# snc98_3x4_Switch-futuba.net
KiCad netlist of a schematic drawn in EAGLE
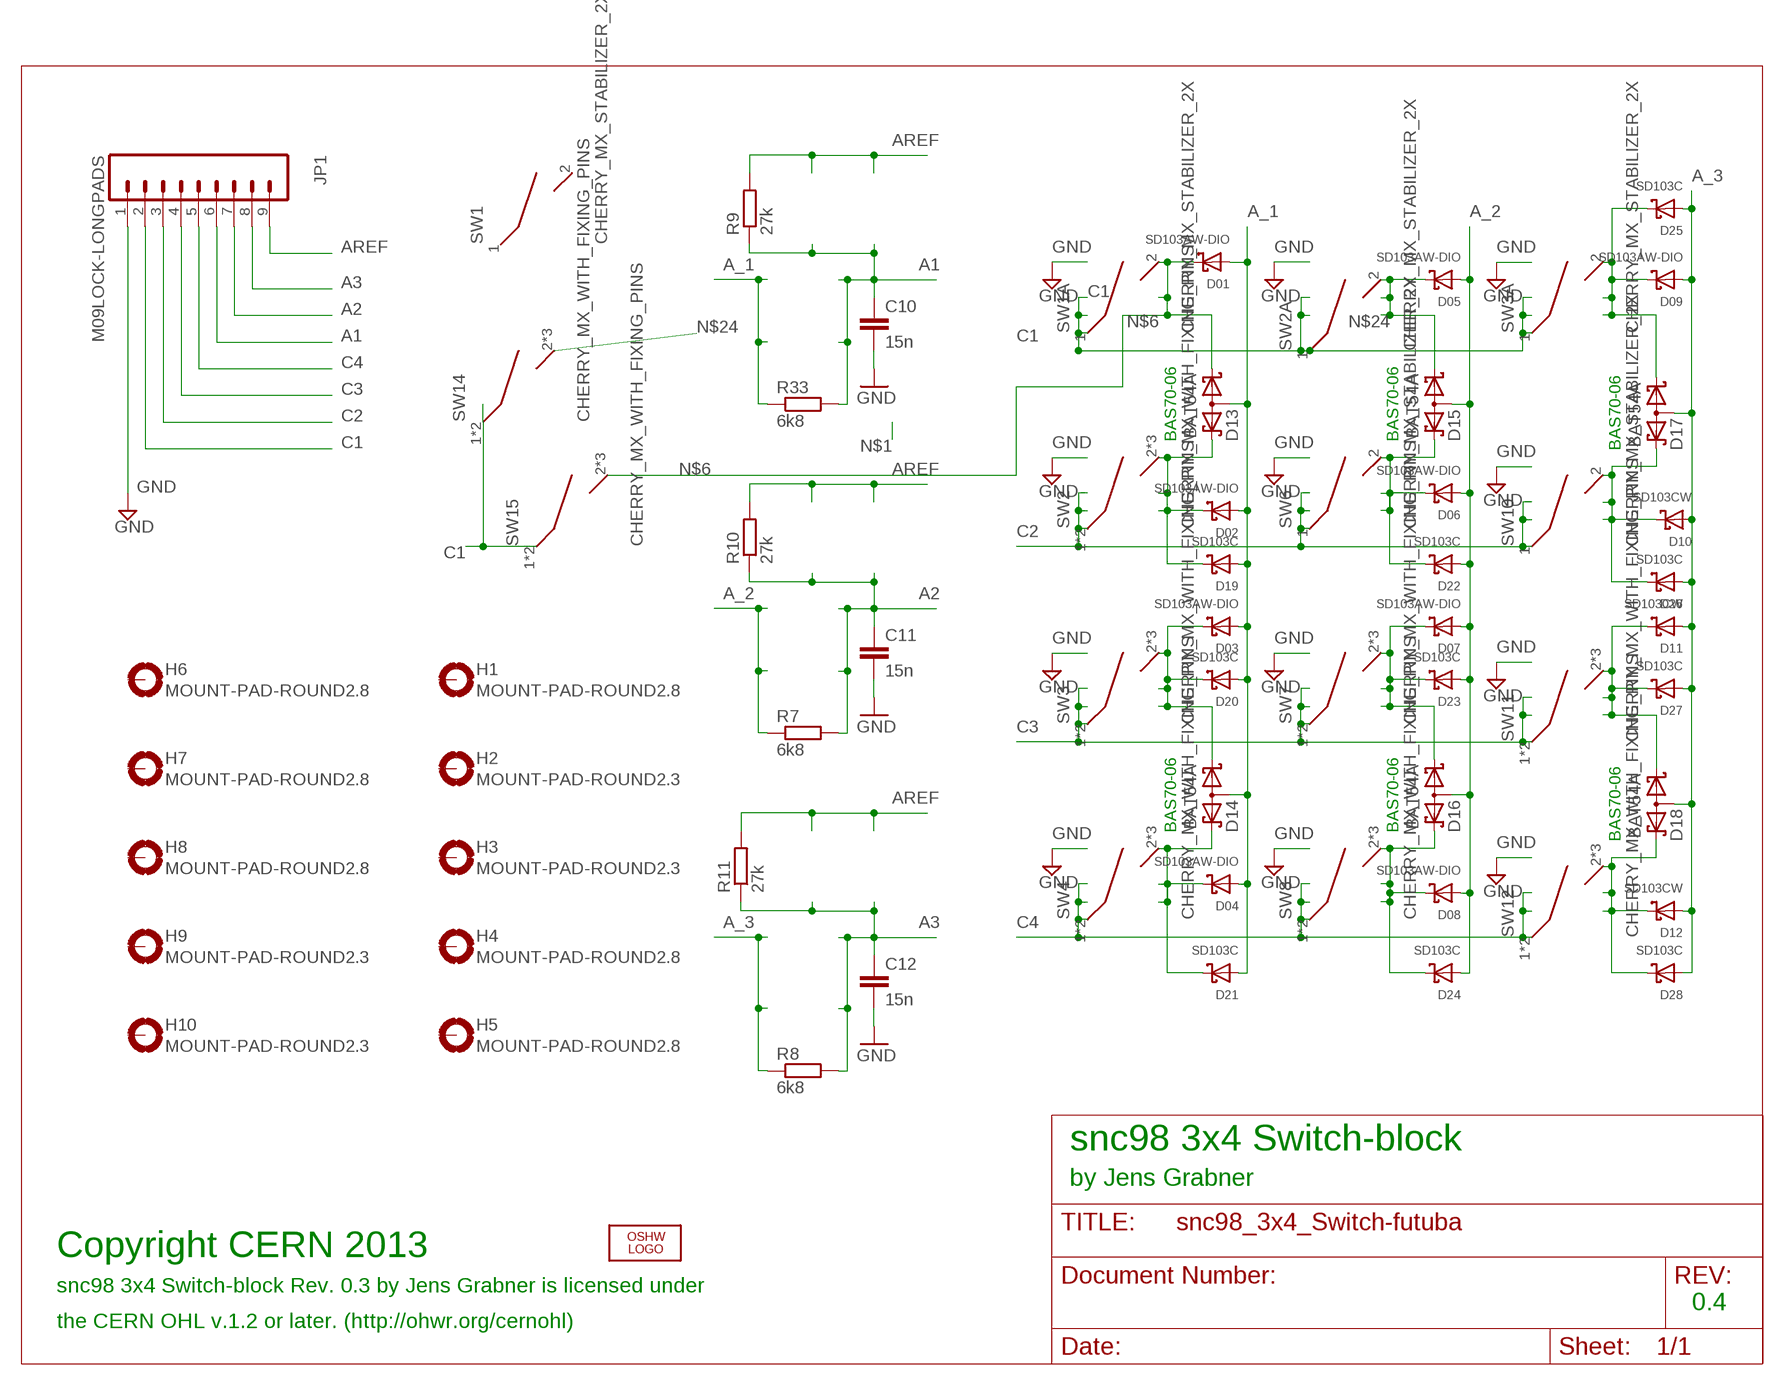
[diagram p0: schematic, sheet 1]

(export (version "E")
  (design (tool "Eeschema 10.0.6"))
  (components
    (comp (ref "C10")
      (value "15n")
      (footprint "eagle-import:C1206K")
      (libsource (lib "eagle-import") (part "C-EUC1206K"))
    )
    (comp (ref "C11")
      (value "15n")
      (footprint "eagle-import:C1206K")
      (libsource (lib "eagle-import") (part "C-EUC1206K"))
    )
    (comp (ref "C12")
      (value "15n")
      (footprint "eagle-import:C1206K")
      (libsource (lib "eagle-import") (part "C-EUC1206K"))
    )
    (comp (ref "D01")
      (value "SD103AW-DIO")
      (footprint "eagle-import:SOD-123F")
      (fields (field (name "MF") "MULTICOMP") (field (name "MPN") "SD103CW-7-F"))
      (libsource (lib "eagle-import") (part "DIODESOD-123F"))
    )
    (comp (ref "D02")
      (value "SD103AW-DIO")
      (footprint "eagle-import:SOD-123F")
      (fields (field (name "MF") "MULTICOMP") (field (name "MPN") "SD103CW-7-F"))
      (libsource (lib "eagle-import") (part "DIODESOD-123F"))
    )
    (comp (ref "D03")
      (value "SD103AW-DIO")
      (footprint "eagle-import:SOD-123F")
      (fields (field (name "MF") "MULTICOMP") (field (name "MPN") "SD103CW-7-F"))
      (libsource (lib "eagle-import") (part "DIODESOD-123F"))
    )
    (comp (ref "D04")
      (value "SD103AW-DIO")
      (footprint "eagle-import:SOD-123F")
      (fields (field (name "MF") "MULTICOMP") (field (name "MPN") "SD103CW-7-F"))
      (libsource (lib "eagle-import") (part "DIODESOD-123F"))
    )
    (comp (ref "D05")
      (value "SD103AW-DIO")
      (footprint "eagle-import:SOD-123F")
      (fields (field (name "MF") "MULTICOMP") (field (name "MPN") "SD103CW-7-F"))
      (libsource (lib "eagle-import") (part "DIODESOD-123F"))
    )
    (comp (ref "D06")
      (value "SD103AW-DIO")
      (footprint "eagle-import:SOD-123F")
      (fields (field (name "MF") "MULTICOMP") (field (name "MPN") "SD103CW-7-F"))
      (libsource (lib "eagle-import") (part "DIODESOD-123F"))
    )
    (comp (ref "D07")
      (value "SD103AW-DIO")
      (footprint "eagle-import:SOD-123F")
      (fields (field (name "MF") "MULTICOMP") (field (name "MPN") "SD103CW-7-F"))
      (libsource (lib "eagle-import") (part "DIODESOD-123F"))
    )
    (comp (ref "D08")
      (value "SD103AW-DIO")
      (footprint "eagle-import:SOD-123F")
      (fields (field (name "MF") "MULTICOMP") (field (name "MPN") "SD103CW-7-F"))
      (libsource (lib "eagle-import") (part "DIODESOD-123F"))
    )
    (comp (ref "D09")
      (value "SD103AW-DIO")
      (footprint "eagle-import:SOD-123F")
      (fields (field (name "MF") "MULTICOMP") (field (name "MPN") "SD103CW-7-F"))
      (libsource (lib "eagle-import") (part "DIODESOD-123F"))
    )
    (comp (ref "D10")
      (value "SD103CW")
      (footprint "eagle-import:SOD-123F")
      (fields (field (name "MF") "MULTICOMP") (field (name "MPN") "SD103CW-7-F"))
      (libsource (lib "eagle-import") (part "DIODESOD-123F"))
    )
    (comp (ref "D11")
      (value "SD103CW")
      (footprint "eagle-import:SOD-123F")
      (fields (field (name "MF") "MULTICOMP") (field (name "MPN") "SD103CW-7-F"))
      (libsource (lib "eagle-import") (part "DIODESOD-123F"))
    )
    (comp (ref "D12")
      (value "SD103CW")
      (footprint "eagle-import:SOD-123F")
      (fields (field (name "MF") "MULTICOMP") (field (name "MPN") "SD103CW-7-F"))
      (libsource (lib "eagle-import") (part "DIODESOD-123F"))
    )
    (comp (ref "D13")
      (value "BAT54A")
      (footprint "eagle-import:SOT23")
      (libsource (lib "eagle-import") (part "BAT54A"))
    )
    (comp (ref "D14")
      (value "BAT54A")
      (footprint "eagle-import:SOT23")
      (libsource (lib "eagle-import") (part "BAT54A"))
    )
    (comp (ref "D15")
      (value "BAT54A")
      (footprint "eagle-import:SOT23")
      (libsource (lib "eagle-import") (part "BAT54A"))
    )
    (comp (ref "D16")
      (value "BAT54A")
      (footprint "eagle-import:SOT23")
      (libsource (lib "eagle-import") (part "BAT54A"))
    )
    (comp (ref "D17")
      (value "BAT54A")
      (footprint "eagle-import:SOT23")
      (libsource (lib "eagle-import") (part "BAT54A"))
    )
    (comp (ref "D18")
      (value "BAT54A")
      (footprint "eagle-import:SOT23")
      (libsource (lib "eagle-import") (part "BAT54A"))
    )
    (comp (ref "D19")
      (value "SD103C")
      (footprint "eagle-import:280MIL-TH")
      (fields (field (name "MF") "MULTICOMP") (field (name "MPN") "SD103CW-7-F"))
      (libsource (lib "eagle-import") (part "DIODE280MIL-TH"))
    )
    (comp (ref "D20")
      (value "SD103C")
      (footprint "eagle-import:280MIL-TH")
      (fields (field (name "MF") "MULTICOMP") (field (name "MPN") "SD103CW-7-F"))
      (libsource (lib "eagle-import") (part "DIODE280MIL-TH"))
    )
    (comp (ref "D21")
      (value "SD103C")
      (footprint "eagle-import:280MIL-TH")
      (fields (field (name "MF") "MULTICOMP") (field (name "MPN") "SD103CW-7-F"))
      (libsource (lib "eagle-import") (part "DIODE280MIL-TH"))
    )
    (comp (ref "D22")
      (value "SD103C")
      (footprint "eagle-import:280MIL-TH")
      (fields (field (name "MF") "MULTICOMP") (field (name "MPN") "SD103CW-7-F"))
      (libsource (lib "eagle-import") (part "DIODE280MIL-TH"))
    )
    (comp (ref "D23")
      (value "SD103C")
      (footprint "eagle-import:280MIL-TH")
      (fields (field (name "MF") "MULTICOMP") (field (name "MPN") "SD103CW-7-F"))
      (libsource (lib "eagle-import") (part "DIODE280MIL-TH"))
    )
    (comp (ref "D24")
      (value "SD103C")
      (footprint "eagle-import:280MIL-TH")
      (fields (field (name "MF") "MULTICOMP") (field (name "MPN") "SD103CW-7-F"))
      (libsource (lib "eagle-import") (part "DIODE280MIL-TH"))
    )
    (comp (ref "D25")
      (value "SD103C")
      (footprint "eagle-import:280MIL-TH")
      (fields (field (name "MF") "MULTICOMP") (field (name "MPN") "SD103CW-7-F"))
      (libsource (lib "eagle-import") (part "DIODE280MIL-TH"))
    )
    (comp (ref "D26")
      (value "SD103C")
      (footprint "eagle-import:280MIL-TH")
      (fields (field (name "MF") "MULTICOMP") (field (name "MPN") "SD103CW-7-F"))
      (libsource (lib "eagle-import") (part "DIODE280MIL-TH"))
    )
    (comp (ref "D27")
      (value "SD103C")
      (footprint "eagle-import:280MIL-TH")
      (fields (field (name "MF") "MULTICOMP") (field (name "MPN") "SD103CW-7-F"))
      (libsource (lib "eagle-import") (part "DIODE280MIL-TH"))
    )
    (comp (ref "D28")
      (value "SD103C")
      (footprint "eagle-import:280MIL-TH")
      (fields (field (name "MF") "MULTICOMP") (field (name "MPN") "SD103CW-7-F"))
      (libsource (lib "eagle-import") (part "DIODE280MIL-TH"))
    )
    (comp (ref "H1")
      (value "MOUNT-PAD-ROUND2.8")
      (footprint "eagle-import:2,8-PAD")
      (libsource (lib "eagle-import") (part "MOUNT-PAD-ROUND2.8"))
    )
    (comp (ref "H2")
      (value "MOUNT-PAD-ROUND2.3")
      (footprint "eagle-import:2,3-PAD")
      (libsource (lib "eagle-import") (part "MOUNT-PAD-ROUND2.3"))
    )
    (comp (ref "H3")
      (value "MOUNT-PAD-ROUND2.3")
      (footprint "eagle-import:2,3-PAD")
      (libsource (lib "eagle-import") (part "MOUNT-PAD-ROUND2.3"))
    )
    (comp (ref "H4")
      (value "MOUNT-PAD-ROUND2.8")
      (footprint "eagle-import:2,8-PAD")
      (libsource (lib "eagle-import") (part "MOUNT-PAD-ROUND2.8"))
    )
    (comp (ref "H5")
      (value "MOUNT-PAD-ROUND2.8")
      (footprint "eagle-import:2,8-PAD")
      (libsource (lib "eagle-import") (part "MOUNT-PAD-ROUND2.8"))
    )
    (comp (ref "H6")
      (value "MOUNT-PAD-ROUND2.8")
      (footprint "eagle-import:2,8-PAD")
      (libsource (lib "eagle-import") (part "MOUNT-PAD-ROUND2.8"))
    )
    (comp (ref "H7")
      (value "MOUNT-PAD-ROUND2.8")
      (footprint "eagle-import:2,8-PAD")
      (libsource (lib "eagle-import") (part "MOUNT-PAD-ROUND2.8"))
    )
    (comp (ref "H8")
      (value "MOUNT-PAD-ROUND2.8")
      (footprint "eagle-import:2,8-PAD")
      (libsource (lib "eagle-import") (part "MOUNT-PAD-ROUND2.8"))
    )
    (comp (ref "H9")
      (value "MOUNT-PAD-ROUND2.3")
      (footprint "eagle-import:2,3-PAD")
      (libsource (lib "eagle-import") (part "MOUNT-PAD-ROUND2.3"))
    )
    (comp (ref "H10")
      (value "MOUNT-PAD-ROUND2.3")
      (footprint "eagle-import:2,3-PAD")
      (libsource (lib "eagle-import") (part "MOUNT-PAD-ROUND2.3"))
    )
    (comp (ref "JP1")
      (value "M09LOCK-LONGPADS")
      (footprint "eagle-import:1X09_LOCK_LONGPADS")
      (libsource (lib "eagle-import") (part "M09LOCK-LONGPADS"))
    )
    (comp (ref "LOGO1")
      (value "OSHW_LOGO_8MILX0150-NT")
      (footprint "eagle-import:OSHW_8X150_NOTEXT")
      (libsource (lib "eagle-import") (part "OSHW_LOGO_8MILX0150-NT"))
    )
    (comp (ref "R7")
      (value "6k8")
      (footprint "eagle-import:M0805")
      (libsource (lib "eagle-import") (part "R-EU_M0805"))
    )
    (comp (ref "R8")
      (value "6k8")
      (footprint "eagle-import:M0805")
      (libsource (lib "eagle-import") (part "R-EU_M0805"))
    )
    (comp (ref "R9")
      (value "27k")
      (footprint "eagle-import:M0805")
      (libsource (lib "eagle-import") (part "R-EU_M0805"))
    )
    (comp (ref "R10")
      (value "27k")
      (footprint "eagle-import:M0805")
      (libsource (lib "eagle-import") (part "R-EU_M0805"))
    )
    (comp (ref "R11")
      (value "27k")
      (footprint "eagle-import:M0805")
      (libsource (lib "eagle-import") (part "R-EU_M0805"))
    )
    (comp (ref "R33")
      (value "6k8")
      (footprint "eagle-import:M0805")
      (libsource (lib "eagle-import") (part "R-EU_M0805"))
    )
    (comp (ref "SW1")
      (value "CHERRY_MX_STABILIZER_2X")
      (footprint "eagle-import:MX1A-XXNN_WITH_STABILIZER_2X")
      (libsource (lib "eagle-import") (part "CHERRY_MX_STABILIZER_2X"))
    )
    (comp (ref "SW1A")
      (value "CHERRY_MX_STABILIZER_2X")
      (footprint "eagle-import:MX1A-XXNN_WITH_STABILIZER_2X")
      (libsource (lib "eagle-import") (part "CHERRY_MX_STABILIZER_2X"))
    )
    (comp (ref "SW2")
      (value "CHERRY_MX_WITH_FIXING_PINS")
      (footprint "eagle-import:MX1A-XXNW")
      (libsource (lib "eagle-import") (part "CHERRY_MX_WITH_FIXING_PINS"))
    )
    (comp (ref "SW2A")
      (value "CHERRY_MX_STABILIZER_2X")
      (footprint "eagle-import:MX1A-XXNN_WITH_STABILIZER_2X")
      (libsource (lib "eagle-import") (part "CHERRY_MX_STABILIZER_2X"))
    )
    (comp (ref "SW3")
      (value "CHERRY_MX_WITH_FIXING_PINS")
      (footprint "eagle-import:MX1A-XXNW")
      (libsource (lib "eagle-import") (part "CHERRY_MX_WITH_FIXING_PINS"))
    )
    (comp (ref "SW3A")
      (value "CHERRY_MX_STABILIZER_2X")
      (footprint "eagle-import:MX1A-XXNN_WITH_STABILIZER_2X")
      (libsource (lib "eagle-import") (part "CHERRY_MX_STABILIZER_2X"))
    )
    (comp (ref "SW4")
      (value "CHERRY_MX_WITH_FIXING_PINS")
      (footprint "eagle-import:MX1A-XXNW")
      (libsource (lib "eagle-import") (part "CHERRY_MX_WITH_FIXING_PINS"))
    )
    (comp (ref "SW6")
      (value "CHERRY_MX_STABILIZER_2X")
      (footprint "eagle-import:MX1A-XXNN_WITH_STABILIZER_2X")
      (libsource (lib "eagle-import") (part "CHERRY_MX_STABILIZER_2X"))
    )
    (comp (ref "SW7")
      (value "CHERRY_MX_WITH_FIXING_PINS")
      (footprint "eagle-import:MX1A-XXNW")
      (libsource (lib "eagle-import") (part "CHERRY_MX_WITH_FIXING_PINS"))
    )
    (comp (ref "SW8")
      (value "CHERRY_MX_WITH_FIXING_PINS")
      (footprint "eagle-import:MX1A-XXNW")
      (libsource (lib "eagle-import") (part "CHERRY_MX_WITH_FIXING_PINS"))
    )
    (comp (ref "SW10")
      (value "CHERRY_MX_STABILIZER_2X")
      (footprint "eagle-import:MX1A-XXNN_WITH_STABILIZER_2X")
      (libsource (lib "eagle-import") (part "CHERRY_MX_STABILIZER_2X"))
    )
    (comp (ref "SW11")
      (value "CHERRY_MX_WITH_FIXING_PINS")
      (footprint "eagle-import:MX1A-XXNW")
      (libsource (lib "eagle-import") (part "CHERRY_MX_WITH_FIXING_PINS"))
    )
    (comp (ref "SW12")
      (value "CHERRY_MX_WITH_FIXING_PINS")
      (footprint "eagle-import:MX1A-XXNW")
      (libsource (lib "eagle-import") (part "CHERRY_MX_WITH_FIXING_PINS"))
    )
    (comp (ref "SW14")
      (value "CHERRY_MX_WITH_FIXING_PINS")
      (footprint "eagle-import:MX1A-XXNW")
      (libsource (lib "eagle-import") (part "CHERRY_MX_WITH_FIXING_PINS"))
    )
    (comp (ref "SW15")
      (value "CHERRY_MX_WITH_FIXING_PINS")
      (footprint "eagle-import:MX1A-XXNW")
      (libsource (lib "eagle-import") (part "CHERRY_MX_WITH_FIXING_PINS"))
    )
  )
  (nets
    (net (code "1") (name "/A1") (class "Default")
      (node (ref "C10") (pin "1") (pinfunction "1_1") (pintype "passive"))
      (node (ref "JP1") (pin "6") (pinfunction "6_6") (pintype "passive"))
      (node (ref "R33") (pin "2") (pinfunction "2_2") (pintype "passive"))
      (node (ref "R9") (pin "1") (pinfunction "1_1") (pintype "passive"))
    )
    (net (code "2") (name "/A2") (class "Default")
      (node (ref "C11") (pin "1") (pinfunction "1_1") (pintype "passive"))
      (node (ref "JP1") (pin "7") (pinfunction "7_7") (pintype "passive"))
      (node (ref "R10") (pin "1") (pinfunction "1_1") (pintype "passive"))
      (node (ref "R7") (pin "2") (pinfunction "2_2") (pintype "passive"))
    )
    (net (code "3") (name "/A3") (class "Default")
      (node (ref "C12") (pin "1") (pinfunction "1_1") (pintype "passive"))
      (node (ref "JP1") (pin "8") (pinfunction "8_8") (pintype "passive"))
      (node (ref "R11") (pin "1") (pinfunction "1_1") (pintype "passive"))
      (node (ref "R8") (pin "2") (pinfunction "2_2") (pintype "passive"))
    )
    (net (code "4") (name "/AREF") (class "Default")
      (node (ref "JP1") (pin "9") (pinfunction "9_9") (pintype "passive"))
      (node (ref "R10") (pin "2") (pinfunction "2_2") (pintype "passive"))
      (node (ref "R11") (pin "2") (pinfunction "2_2") (pintype "passive"))
      (node (ref "R9") (pin "2") (pinfunction "2_2") (pintype "passive"))
    )
    (net (code "5") (name "/A_1") (class "Default")
      (node (ref "D01") (pin "A") (pinfunction "A_A") (pintype "passive"))
      (node (ref "D02") (pin "A") (pinfunction "A_A") (pintype "passive"))
      (node (ref "D03") (pin "A") (pinfunction "A_A") (pintype "passive"))
      (node (ref "D04") (pin "A") (pinfunction "A_A") (pintype "passive"))
      (node (ref "D13") (pin "3") (pinfunction "AA_3") (pintype "passive"))
      (node (ref "D14") (pin "3") (pinfunction "AA_3") (pintype "passive"))
      (node (ref "D19") (pin "P$1") (pinfunction "A_P$1") (pintype "passive"))
      (node (ref "D20") (pin "P$1") (pinfunction "A_P$1") (pintype "passive"))
      (node (ref "D21") (pin "P$1") (pinfunction "A_P$1") (pintype "passive"))
      (node (ref "R33") (pin "1") (pinfunction "1_1") (pintype "passive"))
    )
    (net (code "6") (name "/A_2") (class "Default")
      (node (ref "D05") (pin "A") (pinfunction "A_A") (pintype "passive"))
      (node (ref "D06") (pin "A") (pinfunction "A_A") (pintype "passive"))
      (node (ref "D07") (pin "A") (pinfunction "A_A") (pintype "passive"))
      (node (ref "D08") (pin "A") (pinfunction "A_A") (pintype "passive"))
      (node (ref "D15") (pin "3") (pinfunction "AA_3") (pintype "passive"))
      (node (ref "D16") (pin "3") (pinfunction "AA_3") (pintype "passive"))
      (node (ref "D22") (pin "P$1") (pinfunction "A_P$1") (pintype "passive"))
      (node (ref "D23") (pin "P$1") (pinfunction "A_P$1") (pintype "passive"))
      (node (ref "D24") (pin "P$1") (pinfunction "A_P$1") (pintype "passive"))
      (node (ref "R7") (pin "1") (pinfunction "1_1") (pintype "passive"))
    )
    (net (code "7") (name "/A_3") (class "Default")
      (node (ref "D09") (pin "A") (pinfunction "A_A") (pintype "passive"))
      (node (ref "D10") (pin "A") (pinfunction "A_A") (pintype "passive"))
      (node (ref "D11") (pin "A") (pinfunction "A_A") (pintype "passive"))
      (node (ref "D12") (pin "A") (pinfunction "A_A") (pintype "passive"))
      (node (ref "D17") (pin "3") (pinfunction "AA_3") (pintype "passive"))
      (node (ref "D18") (pin "3") (pinfunction "AA_3") (pintype "passive"))
      (node (ref "D25") (pin "P$1") (pinfunction "A_P$1") (pintype "passive"))
      (node (ref "D26") (pin "P$1") (pinfunction "A_P$1") (pintype "passive"))
      (node (ref "D27") (pin "P$1") (pinfunction "A_P$1") (pintype "passive"))
      (node (ref "D28") (pin "P$1") (pinfunction "A_P$1") (pintype "passive"))
      (node (ref "R8") (pin "1") (pinfunction "1_1") (pintype "passive"))
    )
    (net (code "8") (name "/C1") (class "Default")
      (node (ref "JP1") (pin "2") (pinfunction "2_2") (pintype "passive"))
      (node (ref "SW14") (pin "1") (pinfunction "1_1") (pintype "passive"))
      (node (ref "SW14") (pin "3") (pinfunction "1_3") (pintype "passive"))
      (node (ref "SW15") (pin "1") (pinfunction "1_1") (pintype "passive"))
      (node (ref "SW15") (pin "3") (pinfunction "1_3") (pintype "passive"))
      (node (ref "SW1A") (pin "1") (pinfunction "1_1") (pintype "passive"))
      (node (ref "SW2A") (pin "1") (pinfunction "1_1") (pintype "passive"))
      (node (ref "SW3A") (pin "1") (pinfunction "1_1") (pintype "passive"))
    )
    (net (code "9") (name "/C2") (class "Default")
      (node (ref "JP1") (pin "3") (pinfunction "3_3") (pintype "passive"))
      (node (ref "SW10") (pin "1") (pinfunction "1_1") (pintype "passive"))
      (node (ref "SW2") (pin "1") (pinfunction "1_1") (pintype "passive"))
      (node (ref "SW2") (pin "3") (pinfunction "1_3") (pintype "passive"))
      (node (ref "SW6") (pin "1") (pinfunction "1_1") (pintype "passive"))
    )
    (net (code "10") (name "/C3") (class "Default")
      (node (ref "JP1") (pin "4") (pinfunction "4_4") (pintype "passive"))
      (node (ref "SW11") (pin "1") (pinfunction "1_1") (pintype "passive"))
      (node (ref "SW11") (pin "3") (pinfunction "1_3") (pintype "passive"))
      (node (ref "SW3") (pin "1") (pinfunction "1_1") (pintype "passive"))
      (node (ref "SW3") (pin "3") (pinfunction "1_3") (pintype "passive"))
      (node (ref "SW7") (pin "1") (pinfunction "1_1") (pintype "passive"))
      (node (ref "SW7") (pin "3") (pinfunction "1_3") (pintype "passive"))
    )
    (net (code "11") (name "/C4") (class "Default")
      (node (ref "JP1") (pin "5") (pinfunction "5_5") (pintype "passive"))
      (node (ref "SW12") (pin "1") (pinfunction "1_1") (pintype "passive"))
      (node (ref "SW12") (pin "3") (pinfunction "1_3") (pintype "passive"))
      (node (ref "SW4") (pin "1") (pinfunction "1_1") (pintype "passive"))
      (node (ref "SW4") (pin "3") (pinfunction "1_3") (pintype "passive"))
      (node (ref "SW8") (pin "1") (pinfunction "1_1") (pintype "passive"))
      (node (ref "SW8") (pin "3") (pinfunction "1_3") (pintype "passive"))
    )
    (net (code "13") (name "/N$6") (class "Default")
      (node (ref "D01") (pin "C") (pinfunction "C_C") (pintype "passive"))
      (node (ref "D13") (pin "1") (pinfunction "K1_1") (pintype "passive"))
      (node (ref "SW15") (pin "2") (pinfunction "2_2") (pintype "passive"))
      (node (ref "SW15") (pin "4") (pinfunction "2_4") (pintype "passive"))
      (node (ref "SW15") (pin "5") (pinfunction "2_5") (pintype "passive"))
      (node (ref "SW1A") (pin "2") (pinfunction "2_2") (pintype "passive"))
    )
    (net (code "14") (name "/N$24") (class "Default")
      (node (ref "D05") (pin "C") (pinfunction "C_C") (pintype "passive"))
      (node (ref "D15") (pin "1") (pinfunction "K1_1") (pintype "passive"))
      (node (ref "SW14") (pin "2") (pinfunction "2_2") (pintype "passive"))
      (node (ref "SW14") (pin "4") (pinfunction "2_4") (pintype "passive"))
      (node (ref "SW14") (pin "5") (pinfunction "2_5") (pintype "passive"))
      (node (ref "SW2A") (pin "2") (pinfunction "2_2") (pintype "passive"))
    )
    (net (code "15") (name "GND") (class "Default")
      (node (ref "C10") (pin "2") (pinfunction "2_2") (pintype "passive"))
      (node (ref "C11") (pin "2") (pinfunction "2_2") (pintype "passive"))
      (node (ref "C12") (pin "2") (pinfunction "2_2") (pintype "passive"))
      (node (ref "JP1") (pin "1") (pinfunction "1_1") (pintype "passive"))
    )
    (net (code "16") (name "Net-(D13-K2)") (class "Default")
      (node (ref "D02") (pin "C") (pinfunction "C_C") (pintype "passive"))
      (node (ref "D13") (pin "2") (pinfunction "K2_2") (pintype "passive"))
      (node (ref "D19") (pin "P$2") (pinfunction "C_P$2") (pintype "passive"))
      (node (ref "SW2") (pin "2") (pinfunction "2_2") (pintype "passive"))
      (node (ref "SW2") (pin "4") (pinfunction "2_4") (pintype "passive"))
      (node (ref "SW2") (pin "5") (pinfunction "2_5") (pintype "passive"))
    )
    (net (code "17") (name "Net-(D14-K1)") (class "Default")
      (node (ref "D03") (pin "C") (pinfunction "C_C") (pintype "passive"))
      (node (ref "D14") (pin "1") (pinfunction "K1_1") (pintype "passive"))
      (node (ref "D20") (pin "P$2") (pinfunction "C_P$2") (pintype "passive"))
      (node (ref "SW3") (pin "2") (pinfunction "2_2") (pintype "passive"))
      (node (ref "SW3") (pin "4") (pinfunction "2_4") (pintype "passive"))
      (node (ref "SW3") (pin "5") (pinfunction "2_5") (pintype "passive"))
    )
    (net (code "18") (name "Net-(D14-K2)") (class "Default")
      (node (ref "D04") (pin "C") (pinfunction "C_C") (pintype "passive"))
      (node (ref "D14") (pin "2") (pinfunction "K2_2") (pintype "passive"))
      (node (ref "D21") (pin "P$2") (pinfunction "C_P$2") (pintype "passive"))
      (node (ref "SW4") (pin "2") (pinfunction "2_2") (pintype "passive"))
      (node (ref "SW4") (pin "4") (pinfunction "2_4") (pintype "passive"))
      (node (ref "SW4") (pin "5") (pinfunction "2_5") (pintype "passive"))
    )
    (net (code "19") (name "Net-(D15-K2)") (class "Default")
      (node (ref "D06") (pin "C") (pinfunction "C_C") (pintype "passive"))
      (node (ref "D15") (pin "2") (pinfunction "K2_2") (pintype "passive"))
      (node (ref "D22") (pin "P$2") (pinfunction "C_P$2") (pintype "passive"))
      (node (ref "SW6") (pin "2") (pinfunction "2_2") (pintype "passive"))
    )
    (net (code "20") (name "Net-(D16-K1)") (class "Default")
      (node (ref "D07") (pin "C") (pinfunction "C_C") (pintype "passive"))
      (node (ref "D16") (pin "1") (pinfunction "K1_1") (pintype "passive"))
      (node (ref "D23") (pin "P$2") (pinfunction "C_P$2") (pintype "passive"))
      (node (ref "SW7") (pin "2") (pinfunction "2_2") (pintype "passive"))
      (node (ref "SW7") (pin "4") (pinfunction "2_4") (pintype "passive"))
      (node (ref "SW7") (pin "5") (pinfunction "2_5") (pintype "passive"))
    )
    (net (code "21") (name "Net-(D16-K2)") (class "Default")
      (node (ref "D08") (pin "C") (pinfunction "C_C") (pintype "passive"))
      (node (ref "D16") (pin "2") (pinfunction "K2_2") (pintype "passive"))
      (node (ref "D24") (pin "P$2") (pinfunction "C_P$2") (pintype "passive"))
      (node (ref "SW8") (pin "2") (pinfunction "2_2") (pintype "passive"))
      (node (ref "SW8") (pin "4") (pinfunction "2_4") (pintype "passive"))
      (node (ref "SW8") (pin "5") (pinfunction "2_5") (pintype "passive"))
    )
    (net (code "22") (name "Net-(D17-K1)") (class "Default")
      (node (ref "D09") (pin "C") (pinfunction "C_C") (pintype "passive"))
      (node (ref "D17") (pin "1") (pinfunction "K1_1") (pintype "passive"))
      (node (ref "D25") (pin "P$2") (pinfunction "C_P$2") (pintype "passive"))
      (node (ref "SW3A") (pin "2") (pinfunction "2_2") (pintype "passive"))
    )
    (net (code "23") (name "Net-(D17-K2)") (class "Default")
      (node (ref "D10") (pin "C") (pinfunction "C_C") (pintype "passive"))
      (node (ref "D17") (pin "2") (pinfunction "K2_2") (pintype "passive"))
      (node (ref "D26") (pin "P$2") (pinfunction "C_P$2") (pintype "passive"))
      (node (ref "SW10") (pin "2") (pinfunction "2_2") (pintype "passive"))
    )
    (net (code "24") (name "Net-(D18-K1)") (class "Default")
      (node (ref "D11") (pin "C") (pinfunction "C_C") (pintype "passive"))
      (node (ref "D18") (pin "1") (pinfunction "K1_1") (pintype "passive"))
      (node (ref "D27") (pin "P$2") (pinfunction "C_P$2") (pintype "passive"))
      (node (ref "SW11") (pin "2") (pinfunction "2_2") (pintype "passive"))
      (node (ref "SW11") (pin "4") (pinfunction "2_4") (pintype "passive"))
      (node (ref "SW11") (pin "5") (pinfunction "2_5") (pintype "passive"))
    )
    (net (code "25") (name "Net-(D18-K2)") (class "Default")
      (node (ref "D12") (pin "C") (pinfunction "C_C") (pintype "passive"))
      (node (ref "D18") (pin "2") (pinfunction "K2_2") (pintype "passive"))
      (node (ref "D28") (pin "P$2") (pinfunction "C_P$2") (pintype "passive"))
      (node (ref "SW12") (pin "2") (pinfunction "2_2") (pintype "passive"))
      (node (ref "SW12") (pin "4") (pinfunction "2_4") (pintype "passive"))
      (node (ref "SW12") (pin "5") (pinfunction "2_5") (pintype "passive"))
    )
    (net (code "26") (name "unconnected-(H1-MOUNT-PadB2,8)") (class "Default")
      (node (ref "H1") (pin "B2,8") (pinfunction "MOUNT_B2,8") (pintype "passive"))
    )
    (net (code "27") (name "unconnected-(H2-MOUNT-PadB2,8)") (class "Default")
      (node (ref "H2") (pin "B2,8") (pinfunction "MOUNT_B2,8") (pintype "passive"))
    )
    (net (code "28") (name "unconnected-(H3-MOUNT-PadB2,8)") (class "Default")
      (node (ref "H3") (pin "B2,8") (pinfunction "MOUNT_B2,8") (pintype "passive"))
    )
    (net (code "29") (name "unconnected-(H4-MOUNT-PadB2,8)") (class "Default")
      (node (ref "H4") (pin "B2,8") (pinfunction "MOUNT_B2,8") (pintype "passive"))
    )
    (net (code "30") (name "unconnected-(H5-MOUNT-PadB2,8)") (class "Default")
      (node (ref "H5") (pin "B2,8") (pinfunction "MOUNT_B2,8") (pintype "passive"))
    )
    (net (code "31") (name "unconnected-(H6-MOUNT-PadB2,8)") (class "Default")
      (node (ref "H6") (pin "B2,8") (pinfunction "MOUNT_B2,8") (pintype "passive"))
    )
    (net (code "32") (name "unconnected-(H7-MOUNT-PadB2,8)") (class "Default")
      (node (ref "H7") (pin "B2,8") (pinfunction "MOUNT_B2,8") (pintype "passive"))
    )
    (net (code "33") (name "unconnected-(H8-MOUNT-PadB2,8)") (class "Default")
      (node (ref "H8") (pin "B2,8") (pinfunction "MOUNT_B2,8") (pintype "passive"))
    )
    (net (code "34") (name "unconnected-(H9-MOUNT-PadB2,8)") (class "Default")
      (node (ref "H9") (pin "B2,8") (pinfunction "MOUNT_B2,8") (pintype "passive"))
    )
    (net (code "35") (name "unconnected-(H10-MOUNT-PadB2,8)") (class "Default")
      (node (ref "H10") (pin "B2,8") (pinfunction "MOUNT_B2,8") (pintype "passive"))
    )
    (net (code "36") (name "unconnected-(SW1-Pad1)") (class "Default")
      (node (ref "SW1") (pin "1") (pinfunction "1_1") (pintype "passive"))
    )
    (net (code "37") (name "unconnected-(SW1-Pad2)") (class "Default")
      (node (ref "SW1") (pin "2") (pinfunction "2_2") (pintype "passive"))
    )
  )
)
